# battery_board.net
KiCad netlist of a schematic drawn in Altium Designer
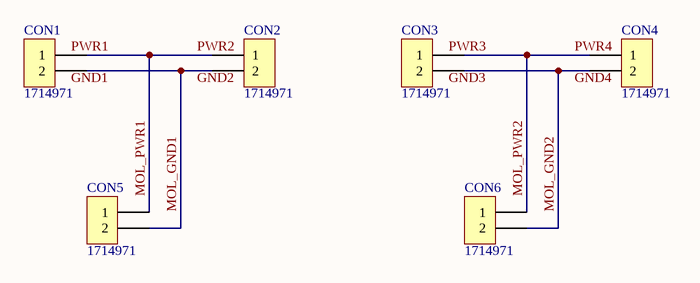
[diagram p0: battery_board.SchDoc]

(export (version "E")
  (design (tool "Eeschema 10.0.6"))
  (components
    (comp (ref "CON1")
      (value "1714971")
      (footprint "1714971")
      (description "2 position screw terminal block 30A")
      (fields (field (name "DIGIKEY PART NUMBER") "277-1271-ND"))
      (libsource (lib "Phoenix") (part "1714971"))
    )
    (comp (ref "CON2")
      (value "1714971")
      (footprint "1714971")
      (description "2 position screw terminal block 30A")
      (fields (field (name "DIGIKEY PART NUMBER") "277-1271-ND"))
      (libsource (lib "") (part "1714971_1"))
    )
    (comp (ref "CON3")
      (value "1714971")
      (footprint "1714971")
      (description "2 position screw terminal block 30A")
      (fields (field (name "DIGIKEY PART NUMBER") "277-1271-ND"))
      (libsource (lib "Phoenix") (part "1714971"))
    )
    (comp (ref "CON4")
      (value "1714971")
      (footprint "1714971")
      (description "2 position screw terminal block 30A")
      (fields (field (name "DIGIKEY PART NUMBER") "277-1271-ND"))
      (libsource (lib "") (part "1714971_1"))
    )
    (comp (ref "CON5")
      (value "1714971")
      (footprint "1714971")
      (description "2 position screw terminal block 30A")
      (fields (field (name "DIGIKEY PART NUMBER") "277-1271-ND"))
      (libsource (lib "Phoenix") (part "1714971"))
    )
    (comp (ref "CON6")
      (value "1714971")
      (footprint "1714971")
      (description "2 position screw terminal block 30A")
      (fields (field (name "DIGIKEY PART NUMBER") "277-1271-ND"))
      (libsource (lib "Phoenix") (part "1714971"))
    )
  )
  (nets
    (net (code "5") (name "/MOL_GND1") (class "Default")
      (node (ref "CON1") (pin "2") (pinfunction "2_2") (pintype "passive"))
      (node (ref "CON2") (pin "2") (pinfunction "2_2") (pintype "passive"))
      (node (ref "CON5") (pin "2") (pinfunction "2_2") (pintype "passive"))
    )
    (net (code "6") (name "/MOL_GND2") (class "Default")
      (node (ref "CON3") (pin "2") (pinfunction "2_2") (pintype "passive"))
      (node (ref "CON4") (pin "2") (pinfunction "2_2") (pintype "passive"))
      (node (ref "CON6") (pin "2") (pinfunction "2_2") (pintype "passive"))
    )
    (net (code "7") (name "/MOL_PWR1") (class "Default")
      (node (ref "CON1") (pin "1") (pinfunction "1_1") (pintype "passive"))
      (node (ref "CON2") (pin "1") (pinfunction "1_1") (pintype "passive"))
      (node (ref "CON5") (pin "1") (pinfunction "1_1") (pintype "passive"))
    )
    (net (code "8") (name "/MOL_PWR2") (class "Default")
      (node (ref "CON3") (pin "1") (pinfunction "1_1") (pintype "passive"))
      (node (ref "CON4") (pin "1") (pinfunction "1_1") (pintype "passive"))
      (node (ref "CON6") (pin "1") (pinfunction "1_1") (pintype "passive"))
    )
  )
)
